# amp_test2.net
KiCad netlist of a schematic drawn in EAGLE
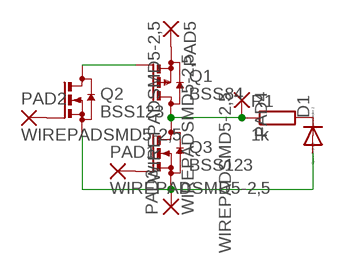
[diagram p0: schematic, sheet 1]

(export (version "E")
  (design (tool "Eeschema 10.0.6"))
  (components
    (comp (ref "D1")
      (value "DIODE-SOD323-R")
      (footprint "eagle-import:SOD323-R")
      (libsource (lib "eagle-import") (part "DIODE-SOD323-R"))
    )
    (comp (ref "PAD1")
      (value "WIREPADSMD5-2,5")
      (footprint "eagle-import:5-2,5")
      (libsource (lib "eagle-import") (part "WIREPADSMD5-2,5"))
    )
    (comp (ref "PAD2")
      (value "WIREPADSMD5-2,5")
      (footprint "eagle-import:5-2,5")
      (libsource (lib "eagle-import") (part "WIREPADSMD5-2,5"))
    )
    (comp (ref "PAD3")
      (value "WIREPADSMD5-2,5")
      (footprint "eagle-import:5-2,5")
      (libsource (lib "eagle-import") (part "WIREPADSMD5-2,5"))
    )
    (comp (ref "PAD4")
      (value "WIREPADSMD5-2,5")
      (footprint "eagle-import:5-2,5")
      (libsource (lib "eagle-import") (part "WIREPADSMD5-2,5"))
    )
    (comp (ref "PAD5")
      (value "WIREPADSMD5-2,5")
      (footprint "eagle-import:5-2,5")
      (libsource (lib "eagle-import") (part "WIREPADSMD5-2,5"))
    )
    (comp (ref "Q1")
      (value "BSS84")
      (footprint "eagle-import:SOT23")
      (libsource (lib "eagle-import") (part "BSS84"))
    )
    (comp (ref "Q2")
      (value "BSS123")
      (footprint "eagle-import:SOT23")
      (libsource (lib "eagle-import") (part "BSS123"))
    )
    (comp (ref "Q3")
      (value "BSS123")
      (footprint "eagle-import:SOT23")
      (libsource (lib "eagle-import") (part "BSS123"))
    )
    (comp (ref "R1")
      (value "1k")
      (footprint "eagle-import:R0603")
      (libsource (lib "eagle-import") (part "R-EU_R0603"))
    )
  )
  (nets
    (net (code "1") (name "Net-(D1-PadC)") (class "Default")
      (node (ref "D1") (pin "C") (pinfunction "C_C") (pintype "passive"))
      (node (ref "R1") (pin "2") (pinfunction "2_2") (pintype "passive"))
    )
    (net (code "2") (name "Net-(PAD1-P)") (class "Default")
      (node (ref "PAD1") (pin "1") (pinfunction "P_1") (pintype "passive"))
      (node (ref "Q3") (pin "1") (pinfunction "G_1") (pintype "passive"))
    )
    (net (code "3") (name "Net-(PAD2-P)") (class "Default")
      (node (ref "PAD2") (pin "1") (pinfunction "P_1") (pintype "passive"))
      (node (ref "Q2") (pin "1") (pinfunction "G_1") (pintype "passive"))
    )
    (net (code "4") (name "Net-(PAD3-P)") (class "Default")
      (node (ref "D1") (pin "A") (pinfunction "A_A") (pintype "passive"))
      (node (ref "PAD3") (pin "1") (pinfunction "P_1") (pintype "passive"))
      (node (ref "Q2") (pin "2") (pinfunction "S_2") (pintype "passive"))
      (node (ref "Q3") (pin "2") (pinfunction "S_2") (pintype "passive"))
    )
    (net (code "5") (name "Net-(PAD4-P)") (class "Default")
      (node (ref "PAD4") (pin "1") (pinfunction "P_1") (pintype "passive"))
      (node (ref "Q1") (pin "3") (pinfunction "D_3") (pintype "passive"))
      (node (ref "Q3") (pin "3") (pinfunction "D_3") (pintype "passive"))
      (node (ref "R1") (pin "1") (pinfunction "1_1") (pintype "passive"))
    )
    (net (code "6") (name "Net-(PAD5-P)") (class "Default")
      (node (ref "PAD5") (pin "1") (pinfunction "P_1") (pintype "passive"))
      (node (ref "Q1") (pin "2") (pinfunction "S_2") (pintype "passive"))
    )
    (net (code "7") (name "Net-(Q1-G)") (class "Default")
      (node (ref "Q1") (pin "1") (pinfunction "G_1") (pintype "passive"))
      (node (ref "Q2") (pin "3") (pinfunction "D_3") (pintype "passive"))
    )
  )
)
